# Motor0.net
KiCad netlist of a schematic drawn in Altium Designer
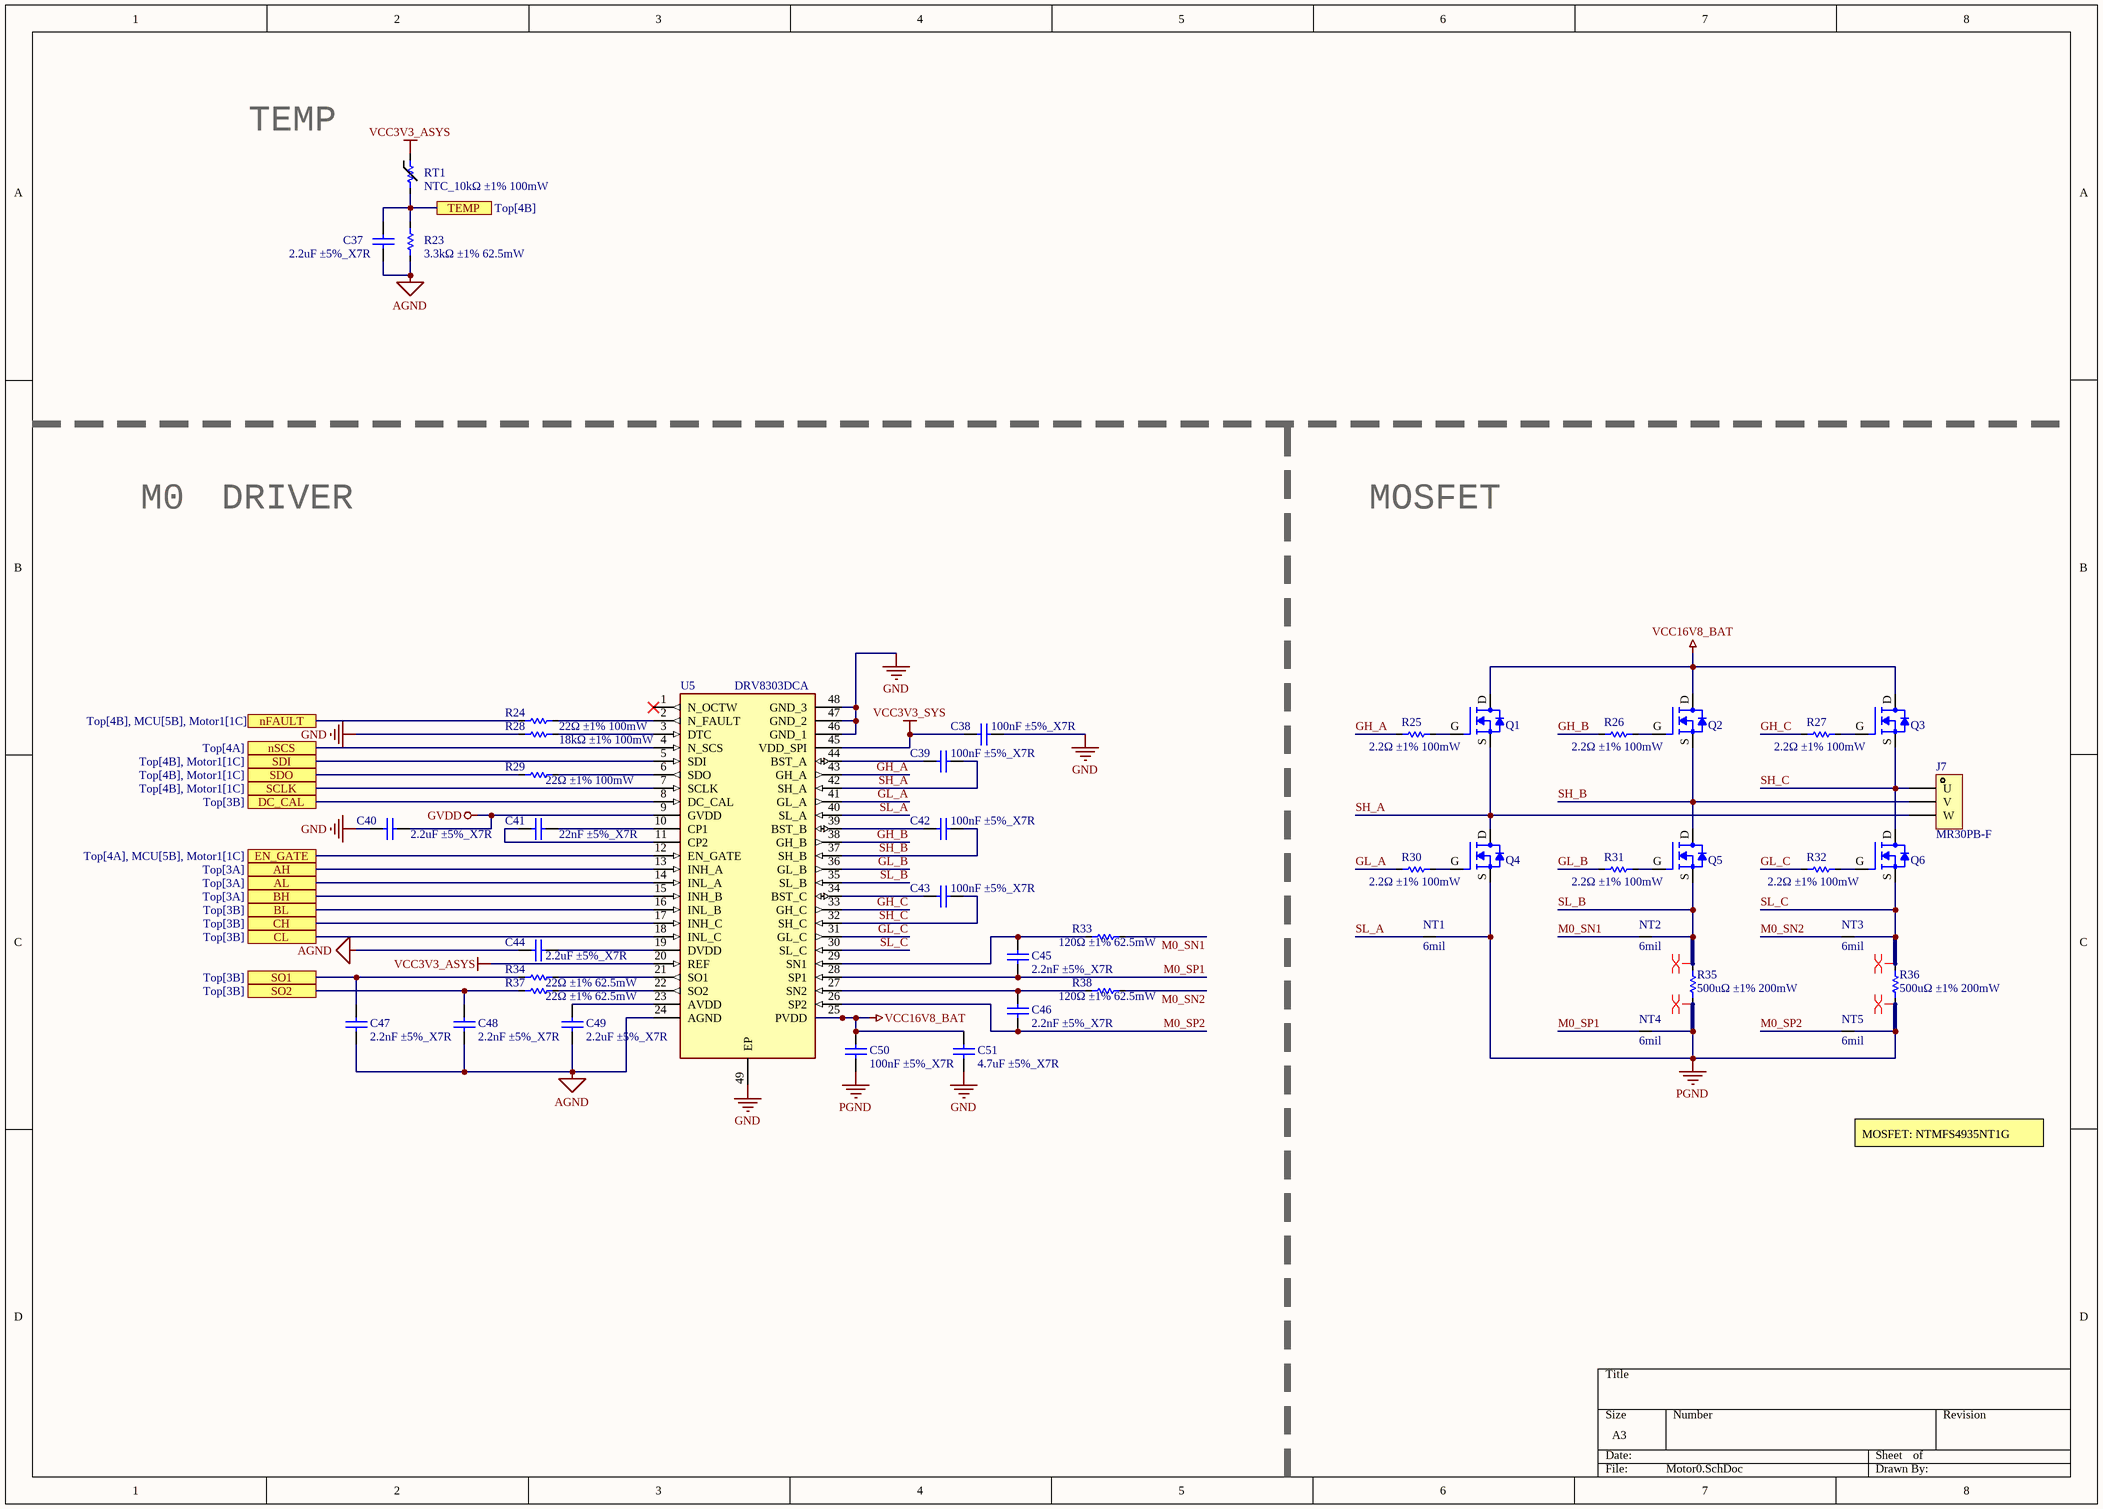
[diagram p0: Motor0.SchDoc]

(export (version "E")
  (design (tool "Eeschema 10.0.6"))
  (components
    (comp (ref "C37")
      (value "2.2uF ±5%_X7R")
      (footprint "WCAP-CSGP_0402_L1W0.5H0.5")
      (description "Capacitor")
      (fields (field (name "PUBLISHER") "Altium Limited"))
      (libsource (lib "Component") (part "Cap"))
    )
    (comp (ref "C38")
      (value "100nF ±5%_X7R")
      (footprint "WCAP-CSGP_0402_L1W0.5H0.5")
      (description "Capacitor")
      (fields (field (name "PUBLISHER") "Altium Limited"))
      (libsource (lib "Component") (part "Cap"))
    )
    (comp (ref "C39")
      (value "100nF ±5%_X7R")
      (footprint "WCAP-CSGP_0402_L1W0.5H0.5")
      (description "Capacitor")
      (fields (field (name "PUBLISHER") "Altium Limited"))
      (libsource (lib "Component") (part "Cap"))
    )
    (comp (ref "C40")
      (value "2.2uF ±5%_X7R")
      (footprint "WCAP-CSGP_0402_L1W0.5H0.5")
      (description "CL05A225KO5NQNC")
      (fields (field (name "PUBLISHER") "Altium Limited"))
      (libsource (lib "Component") (part "Cap"))
    )
    (comp (ref "C41")
      (value "22nF ±5%_X7R")
      (footprint "WCAP-CSGP_0402_L1W0.5H0.5")
      (description "Capacitor")
      (fields (field (name "PUBLISHER") "Altium Limited"))
      (libsource (lib "Component") (part "Cap"))
    )
    (comp (ref "C42")
      (value "100nF ±5%_X7R")
      (footprint "WCAP-CSGP_0402_L1W0.5H0.5")
      (description "Capacitor")
      (fields (field (name "PUBLISHER") "Altium Limited"))
      (libsource (lib "Component") (part "Cap"))
    )
    (comp (ref "C43")
      (value "100nF ±5%_X7R")
      (footprint "WCAP-CSGP_0402_L1W0.5H0.5")
      (description "Capacitor")
      (fields (field (name "PUBLISHER") "Altium Limited"))
      (libsource (lib "Component") (part "Cap"))
    )
    (comp (ref "C44")
      (value "2.2uF ±5%_X7R")
      (footprint "WCAP-CSGP_0402_L1W0.5H0.5")
      (description "CL05A225KO5NQNC")
      (fields (field (name "PUBLISHER") "Altium Limited"))
      (libsource (lib "Component") (part "Cap"))
    )
    (comp (ref "C45")
      (value "2.2nF ±5%_X7R")
      (footprint "WCAP-CSGP_0402_L1W0.5H0.5")
      (description "Capacitor")
      (fields (field (name "PUBLISHER") "Altium Limited"))
      (libsource (lib "Component") (part "Cap"))
    )
    (comp (ref "C46")
      (value "2.2nF ±5%_X7R")
      (footprint "WCAP-CSGP_0402_L1W0.5H0.5")
      (description "Capacitor")
      (fields (field (name "PUBLISHER") "Altium Limited"))
      (libsource (lib "Component") (part "Cap"))
    )
    (comp (ref "C47")
      (value "2.2nF ±5%_X7R")
      (footprint "WCAP-CSGP_0402_L1W0.5H0.5")
      (description "Capacitor")
      (fields (field (name "PUBLISHER") "Altium Limited"))
      (libsource (lib "Component") (part "Cap"))
    )
    (comp (ref "C48")
      (value "2.2nF ±5%_X7R")
      (footprint "WCAP-CSGP_0402_L1W0.5H0.5")
      (description "Capacitor")
      (fields (field (name "PUBLISHER") "Altium Limited"))
      (libsource (lib "Component") (part "Cap"))
    )
    (comp (ref "C49")
      (value "2.2uF ±5%_X7R")
      (footprint "WCAP-CSGP_0402_L1W0.5H0.5")
      (description "CL05A225KO5NQNC")
      (fields (field (name "PUBLISHER") "Altium Limited"))
      (libsource (lib "Component") (part "Cap"))
    )
    (comp (ref "C50")
      (value "100nF ±5%_X7R")
      (footprint "WCAP-CSGP_0402_L1W0.5H0.5")
      (description "Capacitor")
      (fields (field (name "PUBLISHER") "Altium Limited"))
      (libsource (lib "Component") (part "Cap"))
    )
    (comp (ref "C51")
      (value "4.7uF ±5%_X7R")
      (footprint "WCAP-CSGP_0603_L1.6W0.8H0.8_Reflow")
      (description "Capacitor")
      (fields (field (name "PUBLISHER") "Altium Limited"))
      (libsource (lib "Component") (part "Cap"))
    )
    (comp (ref "J7")
      (value "MR30PB-F")
      (footprint "MR30PB-F [Straight] [SMT]")
      (description "驱动器端")
      (libsource (lib "Connectivity_Plugs") (part "MR30PB-F [Straight] [SMT]"))
    )
    (comp (ref "NT1") (value "6mil") (footprint "NETTIE_6mil") (libsource (lib "Component") (part "NETTIE")))
    (comp (ref "NT2") (value "6mil") (footprint "NETTIE_6mil") (libsource (lib "Component") (part "NETTIE")))
    (comp (ref "NT3") (value "6mil") (footprint "NETTIE_6mil") (libsource (lib "Component") (part "NETTIE")))
    (comp (ref "NT4") (value "6mil") (footprint "NETTIE_6mil") (libsource (lib "Component") (part "NETTIE")))
    (comp (ref "NT5") (value "6mil") (footprint "NETTIE_6mil") (libsource (lib "Component") (part "NETTIE")))
    (comp (ref "Q1")
      (value "BSC027N04LSG")
      (footprint "NRVTS10100EMFST1G")
      (description "MOSFET – Power, Single,\r\nN-Channel, PG-TDSON-8\r\nSuperSO8 5x6\r\n40 V, 139 A")
      (fields
        (field (name "MANUFACTURER") "ON Semiconductor")
        (field (name "MANUFACTURER PART NUMBER") "NTMFS4935NT1G")
      )
      (libsource (lib "Component") (part "MOSFET-N"))
    )
    (comp (ref "Q2")
      (value "BSC027N04LSG")
      (footprint "NRVTS10100EMFST1G")
      (description "MOSFET – Power, Single,\r\nN-Channel, PG-TDSON-8\r\nSuperSO8 5x6\r\n40 V, 139 A")
      (fields
        (field (name "MANUFACTURER") "ON Semiconductor")
        (field (name "MANUFACTURER PART NUMBER") "NTMFS4935NT1G")
      )
      (libsource (lib "Component") (part "MOSFET-N"))
    )
    (comp (ref "Q3")
      (value "BSC027N04LSG")
      (footprint "NRVTS10100EMFST1G")
      (description "MOSFET – Power, Single,\r\nN-Channel, PG-TDSON-8\r\nSuperSO8 5x6\r\n40 V, 139 A")
      (fields
        (field (name "MANUFACTURER") "ON Semiconductor")
        (field (name "MANUFACTURER PART NUMBER") "NTMFS4935NT1G")
      )
      (libsource (lib "Component") (part "MOSFET-N"))
    )
    (comp (ref "Q4")
      (value "BSC027N04LSG")
      (footprint "NRVTS10100EMFST1G")
      (description "MOSFET – Power, Single,\r\nN-Channel, PG-TDSON-8\r\nSuperSO8 5x6\r\n40 V, 139 A")
      (fields
        (field (name "MANUFACTURER") "ON Semiconductor")
        (field (name "MANUFACTURER PART NUMBER") "NTMFS4935NT1G")
      )
      (libsource (lib "Component") (part "MOSFET-N"))
    )
    (comp (ref "Q5")
      (value "BSC027N04LSG")
      (footprint "NRVTS10100EMFST1G")
      (description "MOSFET – Power, Single,\r\nN-Channel, PG-TDSON-8\r\nSuperSO8 5x6\r\n40 V, 139 A")
      (fields
        (field (name "MANUFACTURER") "ON Semiconductor")
        (field (name "MANUFACTURER PART NUMBER") "NTMFS4935NT1G")
      )
      (libsource (lib "Component") (part "MOSFET-N"))
    )
    (comp (ref "Q6")
      (value "BSC027N04LSG")
      (footprint "NRVTS10100EMFST1G")
      (description "MOSFET – Power, Single,\r\nN-Channel, PG-TDSON-8\r\nSuperSO8 5x6\r\n40 V, 139 A")
      (fields
        (field (name "MANUFACTURER") "ON Semiconductor")
        (field (name "MANUFACTURER PART NUMBER") "NTMFS4935NT1G")
      )
      (libsource (lib "Component") (part "MOSFET-N"))
    )
    (comp (ref "R23")
      (value "3.3kΩ ±1% 62.5mW")
      (footprint "WRIS-KSKE_0402")
      (description "Resistor")
      (fields (field (name "PUBLISHER") "Altium Limited"))
      (libsource (lib "Component") (part "Res"))
    )
    (comp (ref "R24")
      (value "22Ω ±1% 100mW")
      (footprint "WRIS-KSKE_0402")
      (description "Resistor")
      (fields (field (name "PUBLISHER") "Altium Limited"))
      (libsource (lib "Component") (part "Res"))
    )
    (comp (ref "R25")
      (value "2.2Ω ±1% 100mW")
      (footprint "WRIS-KSKE_0402")
      (description "Resistor")
      (fields (field (name "PUBLISHER") "Altium Limited"))
      (libsource (lib "Component") (part "Res"))
    )
    (comp (ref "R26")
      (value "2.2Ω ±1% 100mW")
      (footprint "WRIS-KSKE_0402")
      (description "Resistor")
      (fields (field (name "PUBLISHER") "Altium Limited"))
      (libsource (lib "Component") (part "Res"))
    )
    (comp (ref "R27")
      (value "2.2Ω ±1% 100mW")
      (footprint "WRIS-KSKE_0402")
      (description "Resistor")
      (fields (field (name "PUBLISHER") "Altium Limited"))
      (libsource (lib "Component") (part "Res"))
    )
    (comp (ref "R28")
      (value "18kΩ ±1% 100mW")
      (footprint "WRIS-KSKE_0402")
      (description "Resistor")
      (fields (field (name "PUBLISHER") "Altium Limited"))
      (libsource (lib "Component") (part "Res"))
    )
    (comp (ref "R29")
      (value "22Ω ±1% 100mW")
      (footprint "WRIS-KSKE_0402")
      (description "Resistor")
      (fields (field (name "PUBLISHER") "Altium Limited"))
      (libsource (lib "Component") (part "Res"))
    )
    (comp (ref "R30")
      (value "2.2Ω ±1% 100mW")
      (footprint "WRIS-KSKE_0402")
      (description "Resistor")
      (fields (field (name "PUBLISHER") "Altium Limited"))
      (libsource (lib "Component") (part "Res"))
    )
    (comp (ref "R31")
      (value "2.2Ω ±1% 100mW")
      (footprint "WRIS-KSKE_0402")
      (description "Resistor")
      (fields (field (name "PUBLISHER") "Altium Limited"))
      (libsource (lib "Component") (part "Res"))
    )
    (comp (ref "R32")
      (value "2.2Ω ±1% 100mW")
      (footprint "WRIS-KSKE_0402")
      (description "Resistor")
      (fields (field (name "PUBLISHER") "Altium Limited"))
      (libsource (lib "Component") (part "Res"))
    )
    (comp (ref "R33")
      (value "120Ω ±1% 62.5mW")
      (footprint "WRIS-KSKE_0402")
      (description "Resistor")
      (fields (field (name "PUBLISHER") "Altium Limited"))
      (libsource (lib "Component") (part "Res"))
    )
    (comp (ref "R34")
      (value "22Ω ±1% 62.5mW")
      (footprint "WRIS-KSKE_0402")
      (description "Resistor")
      (fields (field (name "PUBLISHER") "Altium Limited"))
      (libsource (lib "Component") (part "Res"))
    )
    (comp (ref "R35")
      (value "500uΩ ±1% 200mW")
      (footprint "WRIS-KSKE_2512")
      (description "Resistor")
      (fields (field (name "PUBLISHER") "Altium Limited"))
      (libsource (lib "Component") (part "Res"))
    )
    (comp (ref "R36")
      (value "500uΩ ±1% 200mW")
      (footprint "WRIS-KSKE_2512")
      (description "Resistor")
      (fields (field (name "PUBLISHER") "Altium Limited"))
      (libsource (lib "Component") (part "Res"))
    )
    (comp (ref "R37")
      (value "22Ω ±1% 62.5mW")
      (footprint "WRIS-KSKE_0402")
      (description "Resistor")
      (fields (field (name "PUBLISHER") "Altium Limited"))
      (libsource (lib "Component") (part "Res"))
    )
    (comp (ref "R38")
      (value "120Ω ±1% 62.5mW")
      (footprint "WRIS-KSKE_0402")
      (description "Resistor")
      (fields (field (name "PUBLISHER") "Altium Limited"))
      (libsource (lib "Component") (part "Res"))
    )
    (comp (ref "RT1")
      (value "NTC_10kΩ ±1% 100mW")
      (footprint "WRIS-KSKE_0402")
      (description "THERMISTOR 10K OHM NTC 0402 SMD")
      (libsource (lib "Component") (part "TEMP RES"))
    )
    (comp (ref "U5")
      (value "DRV8303DCA")
      (footprint "SamacSys:SOP50P810X120-49N")
      (description "Integrated Circuit")
      (fields (field (name "MOUSER PART NUMBER") "595-DRV8303DCA"))
      (libsource (lib "*") (part "DRV8303DCA"))
    )
  )
  (nets
    (net (code "1") (name "/AH") (class "Default")
      (node (ref "U5") (pin "13") (pinfunction "INH_A_13") (pintype "input"))
    )
    (net (code "2") (name "/AL") (class "Default")
      (node (ref "U5") (pin "14") (pinfunction "INL_A_14") (pintype "input"))
    )
    (net (code "3") (name "/BH") (class "Default")
      (node (ref "U5") (pin "15") (pinfunction "INH_B_15") (pintype "input"))
    )
    (net (code "4") (name "/BL") (class "Default")
      (node (ref "U5") (pin "16") (pinfunction "INL_B_16") (pintype "input"))
    )
    (net (code "5") (name "/CH") (class "Default")
      (node (ref "U5") (pin "17") (pinfunction "INH_C_17") (pintype "input"))
    )
    (net (code "6") (name "/CL") (class "Default")
      (node (ref "U5") (pin "18") (pinfunction "INL_C_18") (pintype "input"))
    )
    (net (code "7") (name "/DC_CAL") (class "Default")
      (node (ref "U5") (pin "8") (pinfunction "DC_CAL_8") (pintype "input"))
    )
    (net (code "8") (name "/EN_GATE") (class "Default")
      (node (ref "U5") (pin "12") (pinfunction "EN_GATE_12") (pintype "input"))
    )
    (net (code "9") (name "/GH_A") (class "Default")
      (node (ref "R25") (pin "1") (pinfunction "1_1") (pintype "passive"))
      (node (ref "U5") (pin "43") (pinfunction "GH_A_43") (pintype "output"))
    )
    (net (code "10") (name "/GH_B") (class "Default")
      (node (ref "R26") (pin "1") (pinfunction "1_1") (pintype "passive"))
      (node (ref "U5") (pin "38") (pinfunction "GH_B_38") (pintype "output"))
    )
    (net (code "11") (name "/GH_C") (class "Default")
      (node (ref "R27") (pin "1") (pinfunction "1_1") (pintype "passive"))
      (node (ref "U5") (pin "33") (pinfunction "GH_C_33") (pintype "output"))
    )
    (net (code "12") (name "/GL_A") (class "Default")
      (node (ref "R30") (pin "1") (pinfunction "1_1") (pintype "passive"))
      (node (ref "U5") (pin "41") (pinfunction "GL_A_41") (pintype "output"))
    )
    (net (code "13") (name "/GL_B") (class "Default")
      (node (ref "R31") (pin "1") (pinfunction "1_1") (pintype "passive"))
      (node (ref "U5") (pin "36") (pinfunction "GL_B_36") (pintype "output"))
    )
    (net (code "14") (name "/GL_C") (class "Default")
      (node (ref "R32") (pin "1") (pinfunction "1_1") (pintype "passive"))
      (node (ref "U5") (pin "31") (pinfunction "GL_C_31") (pintype "output"))
    )
    (net (code "15") (name "/M0_SN1") (class "Default")
      (node (ref "NT2") (pin "1") (pinfunction "1_1") (pintype "passive"))
      (node (ref "R33") (pin "1") (pinfunction "1_1") (pintype "passive"))
    )
    (net (code "16") (name "/M0_SN2") (class "Default")
      (node (ref "NT3") (pin "1") (pinfunction "1_1") (pintype "passive"))
      (node (ref "R38") (pin "1") (pinfunction "1_1") (pintype "passive"))
    )
    (net (code "17") (name "/M0_SP1") (class "Default")
      (node (ref "C45") (pin "1") (pinfunction "1_1") (pintype "passive"))
      (node (ref "NT4") (pin "1") (pinfunction "1_1") (pintype "passive"))
      (node (ref "U5") (pin "28") (pinfunction "SP1_28") (pintype "input"))
    )
    (net (code "18") (name "/M0_SP2") (class "Default")
      (node (ref "C46") (pin "1") (pinfunction "1_1") (pintype "passive"))
      (node (ref "NT5") (pin "1") (pinfunction "1_1") (pintype "passive"))
      (node (ref "U5") (pin "26") (pinfunction "SP2_26") (pintype "input"))
    )
    (net (code "19") (name "/SCLK") (class "Default")
      (node (ref "U5") (pin "7") (pinfunction "SCLK_7") (pintype "input"))
    )
    (net (code "20") (name "/SDI") (class "Default")
      (node (ref "U5") (pin "5") (pinfunction "SDI_5") (pintype "input"))
    )
    (net (code "21") (name "/SDO") (class "Default")
      (node (ref "R29") (pin "1") (pinfunction "1_1") (pintype "passive"))
    )
    (net (code "22") (name "/SH_A") (class "Default")
      (node (ref "C39") (pin "1") (pinfunction "1_1") (pintype "passive"))
      (node (ref "J7") (pin "3") (pinfunction "W_3") (pintype "passive"))
      (node (ref "Q1") (pin "S") (pinfunction "S_S") (pintype "passive"))
      (node (ref "Q4") (pin "D") (pinfunction "D_D") (pintype "passive"))
      (node (ref "U5") (pin "42") (pinfunction "SH_A_42") (pintype "input"))
    )
    (net (code "23") (name "/SH_B") (class "Default")
      (node (ref "C42") (pin "1") (pinfunction "1_1") (pintype "passive"))
      (node (ref "J7") (pin "2") (pinfunction "V_2") (pintype "passive"))
      (node (ref "Q2") (pin "S") (pinfunction "S_S") (pintype "passive"))
      (node (ref "Q5") (pin "D") (pinfunction "D_D") (pintype "passive"))
      (node (ref "U5") (pin "37") (pinfunction "SH_B_37") (pintype "input"))
    )
    (net (code "24") (name "/SH_C") (class "Default")
      (node (ref "C43") (pin "1") (pinfunction "1_1") (pintype "passive"))
      (node (ref "J7") (pin "1") (pinfunction "U_1") (pintype "passive"))
      (node (ref "Q3") (pin "S") (pinfunction "S_S") (pintype "passive"))
      (node (ref "Q6") (pin "D") (pinfunction "D_D") (pintype "passive"))
      (node (ref "U5") (pin "32") (pinfunction "SH_C_32") (pintype "input"))
    )
    (net (code "25") (name "/SL_A") (class "Default")
      (node (ref "NT1") (pin "1") (pinfunction "1_1") (pintype "passive"))
      (node (ref "U5") (pin "40") (pinfunction "SL_A_40") (pintype "input"))
    )
    (net (code "26") (name "/SL_B") (class "Default")
      (node (ref "NT2") (pin "2") (pinfunction "2_2") (pintype "passive"))
      (node (ref "Q5") (pin "S") (pinfunction "S_S") (pintype "passive"))
      (node (ref "R35") (pin "2") (pinfunction "2_2") (pintype "passive"))
      (node (ref "U5") (pin "35") (pinfunction "SL_B_35") (pintype "input"))
    )
    (net (code "27") (name "/SL_C") (class "Default")
      (node (ref "NT3") (pin "2") (pinfunction "2_2") (pintype "passive"))
      (node (ref "Q6") (pin "S") (pinfunction "S_S") (pintype "passive"))
      (node (ref "R36") (pin "2") (pinfunction "2_2") (pintype "passive"))
      (node (ref "U5") (pin "30") (pinfunction "SL_C_30") (pintype "input"))
    )
    (net (code "28") (name "/SO1") (class "Default")
      (node (ref "C47") (pin "2") (pinfunction "2_2") (pintype "passive"))
      (node (ref "R34") (pin "2") (pinfunction "2_2") (pintype "passive"))
    )
    (net (code "29") (name "/SO2") (class "Default")
      (node (ref "C48") (pin "2") (pinfunction "2_2") (pintype "passive"))
      (node (ref "R37") (pin "2") (pinfunction "2_2") (pintype "passive"))
    )
    (net (code "30") (name "/TEMP") (class "Default")
      (node (ref "C37") (pin "2") (pinfunction "2_2") (pintype "passive"))
      (node (ref "R23") (pin "1") (pinfunction "1_1") (pintype "passive"))
      (node (ref "RT1") (pin "2") (pinfunction "2_2") (pintype "passive"))
    )
    (net (code "31") (name "/nFAULT") (class "Default")
      (node (ref "R24") (pin "1") (pinfunction "1_1") (pintype "passive"))
    )
    (net (code "32") (name "/nSCS") (class "Default")
      (node (ref "U5") (pin "4") (pinfunction "N_SCS_4") (pintype "input"))
    )
    (net (code "33") (name "AGND") (class "Default")
      (node (ref "C37") (pin "1") (pinfunction "1_1") (pintype "passive"))
      (node (ref "C44") (pin "2") (pinfunction "2_2") (pintype "passive"))
      (node (ref "C47") (pin "1") (pinfunction "1_1") (pintype "passive"))
      (node (ref "C48") (pin "1") (pinfunction "1_1") (pintype "passive"))
      (node (ref "C49") (pin "1") (pinfunction "1_1") (pintype "passive"))
      (node (ref "R23") (pin "2") (pinfunction "2_2") (pintype "passive"))
      (node (ref "U5") (pin "24") (pinfunction "AGND_24") (pintype "power_in"))
    )
    (net (code "34") (name "GND") (class "Default")
      (node (ref "C38") (pin "1") (pinfunction "1_1") (pintype "passive"))
      (node (ref "C40") (pin "1") (pinfunction "1_1") (pintype "passive"))
      (node (ref "C51") (pin "1") (pinfunction "1_1") (pintype "passive"))
      (node (ref "R28") (pin "2") (pinfunction "2_2") (pintype "passive"))
      (node (ref "U5") (pin "46") (pinfunction "GND_1_46") (pintype "power_in"))
      (node (ref "U5") (pin "47") (pinfunction "GND_2_47") (pintype "power_in"))
      (node (ref "U5") (pin "48") (pinfunction "GND_3_48") (pintype "power_in"))
      (node (ref "U5") (pin "49") (pinfunction "EP_49") (pintype "passive"))
    )
    (net (code "35") (name "GVDD") (class "Default")
      (node (ref "C40") (pin "2") (pinfunction "2_2") (pintype "passive"))
      (node (ref "U5") (pin "9") (pinfunction "GVDD_9") (pintype "power_in"))
    )
    (net (code "36") (name "Net-(Q1-PadG)") (class "Default")
      (node (ref "Q1") (pin "G") (pinfunction "G_G") (pintype "passive"))
      (node (ref "R25") (pin "2") (pinfunction "2_2") (pintype "passive"))
    )
    (net (code "37") (name "Net-(Q2-PadG)") (class "Default")
      (node (ref "Q2") (pin "G") (pinfunction "G_G") (pintype "passive"))
      (node (ref "R26") (pin "2") (pinfunction "2_2") (pintype "passive"))
    )
    (net (code "38") (name "Net-(Q3-PadG)") (class "Default")
      (node (ref "Q3") (pin "G") (pinfunction "G_G") (pintype "passive"))
      (node (ref "R27") (pin "2") (pinfunction "2_2") (pintype "passive"))
    )
    (net (code "39") (name "Net-(Q4-PadG)") (class "Default")
      (node (ref "Q4") (pin "G") (pinfunction "G_G") (pintype "passive"))
      (node (ref "R30") (pin "2") (pinfunction "2_2") (pintype "passive"))
    )
    (net (code "40") (name "Net-(Q5-PadG)") (class "Default")
      (node (ref "Q5") (pin "G") (pinfunction "G_G") (pintype "passive"))
      (node (ref "R31") (pin "2") (pinfunction "2_2") (pintype "passive"))
    )
    (net (code "41") (name "Net-(Q6-PadG)") (class "Default")
      (node (ref "Q6") (pin "G") (pinfunction "G_G") (pintype "passive"))
      (node (ref "R32") (pin "2") (pinfunction "2_2") (pintype "passive"))
    )
    (net (code "42") (name "Net-(U5-AVDD)") (class "Default")
      (node (ref "C49") (pin "2") (pinfunction "2_2") (pintype "passive"))
      (node (ref "U5") (pin "23") (pinfunction "AVDD_23") (pintype "power_in"))
    )
    (net (code "43") (name "Net-(U5-BST_A)") (class "Default")
      (node (ref "C39") (pin "2") (pinfunction "2_2") (pintype "passive"))
      (node (ref "U5") (pin "44") (pinfunction "BST_A_44") (pintype "bidirectional"))
    )
    (net (code "44") (name "Net-(U5-BST_B)") (class "Default")
      (node (ref "C42") (pin "2") (pinfunction "2_2") (pintype "passive"))
      (node (ref "U5") (pin "39") (pinfunction "BST_B_39") (pintype "bidirectional"))
    )
    (net (code "45") (name "Net-(U5-BST_C)") (class "Default")
      (node (ref "C43") (pin "2") (pinfunction "2_2") (pintype "passive"))
      (node (ref "U5") (pin "34") (pinfunction "BST_C_34") (pintype "bidirectional"))
    )
    (net (code "46") (name "Net-(U5-CP1)") (class "Default")
      (node (ref "C41") (pin "1") (pinfunction "1_1") (pintype "passive"))
      (node (ref "U5") (pin "10") (pinfunction "CP1_10") (pintype "power_in"))
    )
    (net (code "47") (name "Net-(U5-CP2)") (class "Default")
      (node (ref "C41") (pin "2") (pinfunction "2_2") (pintype "passive"))
      (node (ref "U5") (pin "11") (pinfunction "CP2_11") (pintype "power_in"))
    )
    (net (code "48") (name "Net-(U5-DTC)") (class "Default")
      (node (ref "R28") (pin "1") (pinfunction "1_1") (pintype "passive"))
      (node (ref "U5") (pin "3") (pinfunction "DTC_3") (pintype "input"))
    )
    (net (code "49") (name "Net-(U5-DVDD)") (class "Default")
      (node (ref "C44") (pin "1") (pinfunction "1_1") (pintype "passive"))
      (node (ref "U5") (pin "19") (pinfunction "DVDD_19") (pintype "power_in"))
    )
    (net (code "50") (name "Net-(U5-N_FAULT)") (class "Default")
      (node (ref "R24") (pin "2") (pinfunction "2_2") (pintype "passive"))
      (node (ref "U5") (pin "2") (pinfunction "N_FAULT_2") (pintype "output"))
    )
    (net (code "51") (name "Net-(U5-SDO)") (class "Default")
      (node (ref "R29") (pin "2") (pinfunction "2_2") (pintype "passive"))
      (node (ref "U5") (pin "6") (pinfunction "SDO_6") (pintype "output"))
    )
    (net (code "52") (name "Net-(U5-SN1)") (class "Default")
      (node (ref "C45") (pin "2") (pinfunction "2_2") (pintype "passive"))
      (node (ref "R33") (pin "2") (pinfunction "2_2") (pintype "passive"))
      (node (ref "U5") (pin "29") (pinfunction "SN1_29") (pintype "input"))
    )
    (net (code "53") (name "Net-(U5-SN2)") (class "Default")
      (node (ref "C46") (pin "2") (pinfunction "2_2") (pintype "passive"))
      (node (ref "R38") (pin "2") (pinfunction "2_2") (pintype "passive"))
      (node (ref "U5") (pin "27") (pinfunction "SN2_27") (pintype "input"))
    )
    (net (code "54") (name "Net-(U5-SO1)") (class "Default")
      (node (ref "R34") (pin "1") (pinfunction "1_1") (pintype "passive"))
      (node (ref "U5") (pin "21") (pinfunction "SO1_21") (pintype "output"))
    )
    (net (code "55") (name "Net-(U5-SO2)") (class "Default")
      (node (ref "R37") (pin "1") (pinfunction "1_1") (pintype "passive"))
      (node (ref "U5") (pin "22") (pinfunction "SO2_22") (pintype "output"))
    )
    (net (code "56") (name "PGND") (class "Default")
      (node (ref "C50") (pin "1") (pinfunction "1_1") (pintype "passive"))
      (node (ref "NT1") (pin "2") (pinfunction "2_2") (pintype "passive"))
      (node (ref "NT4") (pin "2") (pinfunction "2_2") (pintype "passive"))
      (node (ref "NT5") (pin "2") (pinfunction "2_2") (pintype "passive"))
      (node (ref "Q4") (pin "S") (pinfunction "S_S") (pintype "passive"))
      (node (ref "R35") (pin "1") (pinfunction "1_1") (pintype "passive"))
      (node (ref "R36") (pin "1") (pinfunction "1_1") (pintype "passive"))
    )
    (net (code "57") (name "VCC3V3_ASYS") (class "Default")
      (node (ref "RT1") (pin "1") (pinfunction "1_1") (pintype "passive"))
      (node (ref "U5") (pin "20") (pinfunction "REF_20") (pintype "input"))
    )
    (net (code "58") (name "VCC3V3_SYS") (class "Default")
      (node (ref "C38") (pin "2") (pinfunction "2_2") (pintype "passive"))
      (node (ref "U5") (pin "45") (pinfunction "VDD_SPI_45") (pintype "power_in"))
    )
    (net (code "59") (name "VCC16V8_BAT") (class "Default")
      (node (ref "C50") (pin "2") (pinfunction "2_2") (pintype "passive"))
      (node (ref "C51") (pin "2") (pinfunction "2_2") (pintype "passive"))
      (node (ref "Q1") (pin "D") (pinfunction "D_D") (pintype "passive"))
      (node (ref "Q2") (pin "D") (pinfunction "D_D") (pintype "passive"))
      (node (ref "Q3") (pin "D") (pinfunction "D_D") (pintype "passive"))
      (node (ref "U5") (pin "25") (pinfunction "PVDD_25") (pintype "power_in"))
    )
    (net (code "60") (name "unconnected-(U5-N_OCTW-Pad1)") (class "Default")
      (node (ref "U5") (pin "1") (pinfunction "N_OCTW_1") (pintype "output+no_connect"))
    )
  )
)
